# ADC.net
KiCad netlist of a schematic drawn in Altium Designer
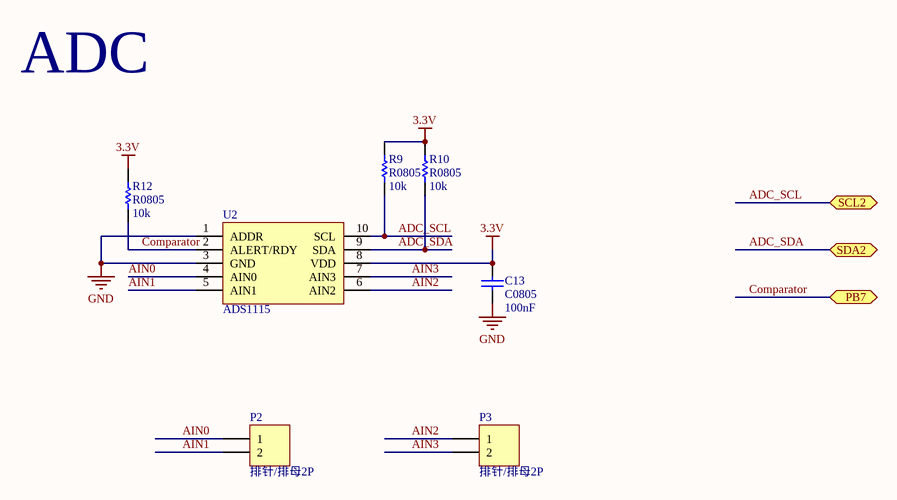
[diagram p0: ADC.SchDoc]

(export (version "E")
  (design (tool "Eeschema 10.0.6"))
  (components
    (comp (ref "C13")
      (value "100nF")
      (footprint "C0805_200X125X140L50N")
      (description "0805 SMT MLCC Capacitor")
      (fields
        (field (name "VOLTAGE") "50V")
        (field (name "TOLERANCE") "10%")
        (field (name "CASE/PACKAGE") "C0805")
        (field (name "PUBLISHER") "Altium Limited")
      )
      (libsource (lib "ayaya0lib") (part "Cap0805"))
    )
    (comp (ref "P2")
      (value "排针/排母2P")
      (footprint "HDR1X2")
      (description "Header, 2-Pin")
      (fields (field (name "PUBLISHER") "Altium Limited"))
      (libsource (lib "earth_ed") (part "Header 2"))
    )
    (comp (ref "P3")
      (value "排针/排母2P")
      (footprint "HDR1X2")
      (description "Header, 2-Pin")
      (fields (field (name "PUBLISHER") "Altium Limited"))
      (libsource (lib "earth_ed") (part "Header 2"))
    )
    (comp (ref "R9")
      (value "10k")
      (footprint "R0805_200X125X140L50N")
      (description "0805 SMT Resistor")
      (fields
        (field (name "TOLERANCE") "1%")
        (field (name "CASE/PACKAGE") "R0805")
        (field (name "PUBLISHER") "Altium Limited")
      )
      (libsource (lib "ayaya0lib") (part "Res0805"))
    )
    (comp (ref "R10")
      (value "10k")
      (footprint "R0805_200X125X140L50N")
      (description "0805 SMT Resistor")
      (fields
        (field (name "TOLERANCE") "1%")
        (field (name "CASE/PACKAGE") "R0805")
        (field (name "PUBLISHER") "Altium Limited")
      )
      (libsource (lib "ayaya0lib") (part "Res0805"))
    )
    (comp (ref "R12")
      (value "10k")
      (footprint "R0805_200X125X140L50N")
      (description "0805 SMT Resistor")
      (fields
        (field (name "TOLERANCE") "1%")
        (field (name "CASE/PACKAGE") "R0805")
        (field (name "PUBLISHER") "Altium Limited")
      )
      (libsource (lib "ayaya0lib") (part "Res0805"))
    )
    (comp (ref "U2")
      (value "ADS1115")
      (footprint "VSSOP-10_L3.0-W3.0-P0.50-LS4.9-BL")
      (fields (field (name "MANUFACTURER") "TI"))
      (libsource (lib "earth_ed") (part "ADS1115"))
    )
  )
  (nets
    (net (code "1") (name "/ADC_SCL") (class "Default")
      (node (ref "R9") (pin "1") (pinfunction "1_1") (pintype "passive"))
      (node (ref "U2") (pin "10") (pinfunction "SCL_10") (pintype "passive"))
    )
    (net (code "2") (name "/ADC_SDA") (class "Default")
      (node (ref "R10") (pin "1") (pinfunction "1_1") (pintype "passive"))
      (node (ref "U2") (pin "9") (pinfunction "SDA_9") (pintype "passive"))
    )
    (net (code "3") (name "/AIN0") (class "Default")
      (node (ref "P2") (pin "1") (pinfunction "1_1") (pintype "passive"))
      (node (ref "U2") (pin "4") (pinfunction "AIN0_4") (pintype "passive"))
    )
    (net (code "4") (name "/AIN1") (class "Default")
      (node (ref "P2") (pin "2") (pinfunction "2_2") (pintype "passive"))
      (node (ref "U2") (pin "5") (pinfunction "AIN1_5") (pintype "passive"))
    )
    (net (code "5") (name "/AIN2") (class "Default")
      (node (ref "P3") (pin "1") (pinfunction "1_1") (pintype "passive"))
      (node (ref "U2") (pin "6") (pinfunction "AIN2_6") (pintype "passive"))
    )
    (net (code "6") (name "/AIN3") (class "Default")
      (node (ref "P3") (pin "2") (pinfunction "2_2") (pintype "passive"))
      (node (ref "U2") (pin "7") (pinfunction "AIN3_7") (pintype "passive"))
    )
    (net (code "7") (name "/Comparator") (class "Default")
      (node (ref "R12") (pin "1") (pinfunction "1_1") (pintype "passive"))
      (node (ref "U2") (pin "2") (pinfunction "ALERT/RDY_2") (pintype "passive"))
    )
    (net (code "8") (name "3.3V") (class "Default")
      (node (ref "C13") (pin "2") (pinfunction "2_2") (pintype "passive"))
      (node (ref "R10") (pin "2") (pinfunction "2_2") (pintype "passive"))
      (node (ref "R12") (pin "2") (pinfunction "2_2") (pintype "passive"))
      (node (ref "R9") (pin "2") (pinfunction "2_2") (pintype "passive"))
      (node (ref "U2") (pin "8") (pinfunction "VDD_8") (pintype "passive"))
    )
    (net (code "9") (name "GND") (class "Default")
      (node (ref "C13") (pin "1") (pinfunction "1_1") (pintype "passive"))
      (node (ref "U2") (pin "1") (pinfunction "ADDR_1") (pintype "passive"))
      (node (ref "U2") (pin "3") (pinfunction "GND_3") (pintype "passive"))
    )
  )
)
